# Pedal_SW.net
KiCad netlist of a schematic drawn in Altium Designer
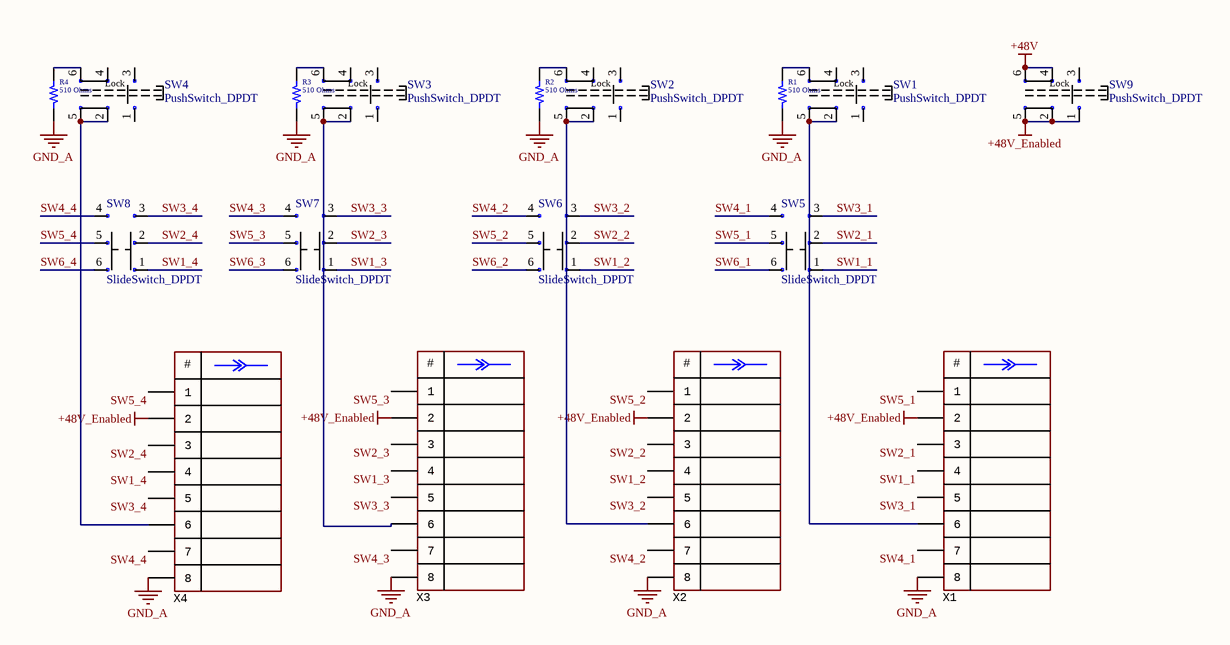
[diagram p0: Pedal_SW.SchDoc]

(export (version "E")
  (design (tool "Eeschema 10.0.6"))
  (components
    (comp (ref "R1")
      (value "510 Ohms")
      (footprint "YAGEO RES 0603_1608")
      (description "RES SMD 510 OHM 1% 1/10W 0603")
      (fields (field (name "PART NUMBER") "AC0603FR-07510RL") (field (name "MANUFACTURER") "Yageo"))
      (libsource (lib "Celestial Altium Library - altium_library") (part "Resistor"))
    )
    (comp (ref "R2")
      (value "510 Ohms")
      (footprint "YAGEO RES 0603_1608")
      (description "RES SMD 510 OHM 1% 1/10W 0603")
      (fields (field (name "PART NUMBER") "AC0603FR-07510RL") (field (name "MANUFACTURER") "Yageo"))
      (libsource (lib "Celestial Altium Library - altium_library") (part "Resistor"))
    )
    (comp (ref "R3")
      (value "510 Ohms")
      (footprint "YAGEO RES 0603_1608")
      (description "RES SMD 510 OHM 1% 1/10W 0603")
      (fields (field (name "PART NUMBER") "AC0603FR-07510RL") (field (name "MANUFACTURER") "Yageo"))
      (libsource (lib "Celestial Altium Library - altium_library") (part "Resistor"))
    )
    (comp (ref "R4")
      (value "510 Ohms")
      (footprint "YAGEO RES 0603_1608")
      (description "RES SMD 510 OHM 1% 1/10W 0603")
      (fields (field (name "PART NUMBER") "AC0603FR-07510RL") (field (name "MANUFACTURER") "Yageo"))
      (libsource (lib "Celestial Altium Library - altium_library") (part "Resistor"))
    )
    (comp (ref "SW1")
      (value "PushSwitch_DPDT")
      (footprint "ProtoStack_H750VBT:TK-6580A-1")
      (libsource (lib "ProtoStack_H750VBT") (part "PushSwitch_DPDT"))
    )
    (comp (ref "SW2")
      (value "PushSwitch_DPDT")
      (footprint "ProtoStack_H750VBT:TK-6580A-1")
      (libsource (lib "ProtoStack_H750VBT") (part "PushSwitch_DPDT"))
    )
    (comp (ref "SW3")
      (value "PushSwitch_DPDT")
      (footprint "ProtoStack_H750VBT:TK-6580A-1")
      (libsource (lib "ProtoStack_H750VBT") (part "PushSwitch_DPDT"))
    )
    (comp (ref "SW4")
      (value "PushSwitch_DPDT")
      (footprint "ProtoStack_H750VBT:TK-6580A-1")
      (libsource (lib "ProtoStack_H750VBT") (part "PushSwitch_DPDT"))
    )
    (comp (ref "SW5")
      (value "SlideSwitch_DPDT")
      (footprint "ProtoStack_H750VBT:SK-22F03-G060")
      (libsource (lib "ProtoStack_H750VBT") (part "SlideSwitch_DPDT"))
    )
    (comp (ref "SW6")
      (value "SlideSwitch_DPDT")
      (footprint "ProtoStack_H750VBT:SK-22F03-G060")
      (libsource (lib "ProtoStack_H750VBT") (part "SlideSwitch_DPDT"))
    )
    (comp (ref "SW7")
      (value "SlideSwitch_DPDT")
      (footprint "ProtoStack_H750VBT:SK-22F03-G060")
      (libsource (lib "ProtoStack_H750VBT") (part "SlideSwitch_DPDT"))
    )
    (comp (ref "SW8")
      (value "SlideSwitch_DPDT")
      (footprint "ProtoStack_H750VBT:SK-22F03-G060")
      (libsource (lib "ProtoStack_H750VBT") (part "SlideSwitch_DPDT"))
    )
    (comp (ref "SW9")
      (value "PushSwitch_DPDT")
      (footprint "ProtoStack_H750VBT:TK-6580A-1")
      (libsource (lib "ProtoStack_H750VBT") (part "PushSwitch_DPDT"))
    )
    (comp (ref "X1")
      (value "~")
      (footprint "CON: PBD-8")
      (fields
        (field (name "MANUFACTURER") "Connfly")
        (field (name "VALUEMANUFACTURERPARTNUMBER") "Connector, 8pin, 2.54mm, 500VAC, 3A")
        (field (name "PARTNUMBER") "PBD-8")
      )
      (libsource (lib "connector") (part "PBD-8"))
    )
    (comp (ref "X2")
      (value "~")
      (footprint "CON: PBD-8")
      (fields
        (field (name "MANUFACTURER") "Connfly")
        (field (name "VALUEMANUFACTURERPARTNUMBER") "Connector, 8pin, 2.54mm, 500VAC, 3A")
        (field (name "PARTNUMBER") "PBD-8")
      )
      (libsource (lib "connector") (part "PBD-8"))
    )
    (comp (ref "X3")
      (value "~")
      (footprint "CON: PBD-8")
      (fields
        (field (name "MANUFACTURER") "Connfly")
        (field (name "VALUEMANUFACTURERPARTNUMBER") "Connector, 8pin, 2.54mm, 500VAC, 3A")
        (field (name "PARTNUMBER") "PBD-8")
      )
      (libsource (lib "connector") (part "PBD-8"))
    )
    (comp (ref "X4")
      (value "~")
      (footprint "CON: PBD-8")
      (fields
        (field (name "MANUFACTURER") "Connfly")
        (field (name "VALUEMANUFACTURERPARTNUMBER") "Connector, 8pin, 2.54mm, 500VAC, 3A")
        (field (name "PARTNUMBER") "PBD-8")
      )
      (libsource (lib "connector") (part "PBD-8"))
    )
  )
  (nets
    (net (code "1") (name "+48V") (class "Default")
      (node (ref "SW9") (pin "4") (pinfunction "4_4") (pintype "passive"))
      (node (ref "SW9") (pin "6") (pinfunction "6_6") (pintype "passive"))
    )
    (net (code "2") (name "+48V_Enabled") (class "Default")
      (node (ref "SW9") (pin "1") (pinfunction "1_1") (pintype "passive"))
      (node (ref "SW9") (pin "2") (pinfunction "2_2") (pintype "passive"))
      (node (ref "SW9") (pin "5") (pinfunction "5_5") (pintype "passive"))
      (node (ref "X1") (pin "2") (pinfunction "2_2") (pintype "passive"))
      (node (ref "X2") (pin "2") (pinfunction "2_2") (pintype "passive"))
      (node (ref "X3") (pin "2") (pinfunction "2_2") (pintype "passive"))
      (node (ref "X4") (pin "2") (pinfunction "2_2") (pintype "passive"))
    )
    (net (code "3") (name "/SW1_1") (class "Default")
      (node (ref "SW5") (pin "1") (pinfunction "1_1") (pintype "passive"))
      (node (ref "X1") (pin "4") (pinfunction "4_4") (pintype "power_in"))
    )
    (net (code "4") (name "/SW1_2") (class "Default")
      (node (ref "SW6") (pin "1") (pinfunction "1_1") (pintype "passive"))
      (node (ref "X2") (pin "4") (pinfunction "4_4") (pintype "power_in"))
    )
    (net (code "5") (name "/SW1_3") (class "Default")
      (node (ref "SW7") (pin "1") (pinfunction "1_1") (pintype "passive"))
      (node (ref "X3") (pin "4") (pinfunction "4_4") (pintype "power_in"))
    )
    (net (code "6") (name "/SW1_4") (class "Default")
      (node (ref "SW8") (pin "1") (pinfunction "1_1") (pintype "passive"))
      (node (ref "X4") (pin "4") (pinfunction "4_4") (pintype "power_in"))
    )
    (net (code "7") (name "/SW2_1") (class "Default")
      (node (ref "SW5") (pin "2") (pinfunction "2_2") (pintype "passive"))
      (node (ref "X1") (pin "3") (pinfunction "3_3") (pintype "power_in"))
    )
    (net (code "8") (name "/SW2_2") (class "Default")
      (node (ref "SW6") (pin "2") (pinfunction "2_2") (pintype "passive"))
      (node (ref "X2") (pin "3") (pinfunction "3_3") (pintype "power_in"))
    )
    (net (code "9") (name "/SW2_3") (class "Default")
      (node (ref "SW7") (pin "2") (pinfunction "2_2") (pintype "passive"))
      (node (ref "X3") (pin "3") (pinfunction "3_3") (pintype "power_in"))
    )
    (net (code "10") (name "/SW2_4") (class "Default")
      (node (ref "SW8") (pin "2") (pinfunction "2_2") (pintype "passive"))
      (node (ref "X4") (pin "3") (pinfunction "3_3") (pintype "power_in"))
    )
    (net (code "11") (name "/SW3_1") (class "Default")
      (node (ref "SW5") (pin "3") (pinfunction "3_3") (pintype "passive"))
      (node (ref "X1") (pin "5") (pinfunction "5_5") (pintype "power_in"))
    )
    (net (code "12") (name "/SW3_2") (class "Default")
      (node (ref "SW6") (pin "3") (pinfunction "3_3") (pintype "passive"))
      (node (ref "X2") (pin "5") (pinfunction "5_5") (pintype "power_in"))
    )
    (net (code "13") (name "/SW3_3") (class "Default")
      (node (ref "SW7") (pin "3") (pinfunction "3_3") (pintype "passive"))
      (node (ref "X3") (pin "5") (pinfunction "5_5") (pintype "power_in"))
    )
    (net (code "14") (name "/SW3_4") (class "Default")
      (node (ref "SW8") (pin "3") (pinfunction "3_3") (pintype "passive"))
      (node (ref "X4") (pin "5") (pinfunction "5_5") (pintype "power_in"))
    )
    (net (code "15") (name "/SW4_1") (class "Default")
      (node (ref "SW5") (pin "4") (pinfunction "4_4") (pintype "passive"))
      (node (ref "X1") (pin "7") (pinfunction "7_7") (pintype "power_in"))
    )
    (net (code "16") (name "/SW4_2") (class "Default")
      (node (ref "SW6") (pin "4") (pinfunction "4_4") (pintype "passive"))
      (node (ref "X2") (pin "7") (pinfunction "7_7") (pintype "power_in"))
    )
    (net (code "17") (name "/SW4_3") (class "Default")
      (node (ref "SW7") (pin "4") (pinfunction "4_4") (pintype "passive"))
      (node (ref "X3") (pin "7") (pinfunction "7_7") (pintype "power_in"))
    )
    (net (code "18") (name "/SW4_4") (class "Default")
      (node (ref "SW8") (pin "4") (pinfunction "4_4") (pintype "passive"))
      (node (ref "X4") (pin "7") (pinfunction "7_7") (pintype "power_in"))
    )
    (net (code "19") (name "/SW5_1") (class "Default")
      (node (ref "SW5") (pin "5") (pinfunction "5_5") (pintype "passive"))
      (node (ref "X1") (pin "1") (pinfunction "1_1") (pintype "passive"))
    )
    (net (code "20") (name "/SW5_2") (class "Default")
      (node (ref "SW6") (pin "5") (pinfunction "5_5") (pintype "passive"))
      (node (ref "X2") (pin "1") (pinfunction "1_1") (pintype "passive"))
    )
    (net (code "21") (name "/SW5_3") (class "Default")
      (node (ref "SW7") (pin "5") (pinfunction "5_5") (pintype "passive"))
      (node (ref "X3") (pin "1") (pinfunction "1_1") (pintype "passive"))
    )
    (net (code "22") (name "/SW5_4") (class "Default")
      (node (ref "SW8") (pin "5") (pinfunction "5_5") (pintype "passive"))
      (node (ref "X4") (pin "1") (pinfunction "1_1") (pintype "passive"))
    )
    (net (code "23") (name "/SW6_1") (class "Default")
      (node (ref "SW5") (pin "6") (pinfunction "6_6") (pintype "passive"))
    )
    (net (code "24") (name "/SW6_2") (class "Default")
      (node (ref "SW6") (pin "6") (pinfunction "6_6") (pintype "passive"))
    )
    (net (code "25") (name "/SW6_3") (class "Default")
      (node (ref "SW7") (pin "6") (pinfunction "6_6") (pintype "passive"))
    )
    (net (code "26") (name "/SW6_4") (class "Default")
      (node (ref "SW8") (pin "6") (pinfunction "6_6") (pintype "passive"))
    )
    (net (code "27") (name "GND_A") (class "Default")
      (node (ref "R1") (pin "2") (pinfunction "2_2") (pintype "passive"))
      (node (ref "R2") (pin "2") (pinfunction "2_2") (pintype "passive"))
      (node (ref "R3") (pin "2") (pinfunction "2_2") (pintype "passive"))
      (node (ref "R4") (pin "2") (pinfunction "2_2") (pintype "passive"))
      (node (ref "X1") (pin "8") (pinfunction "8_8") (pintype "power_in"))
      (node (ref "X2") (pin "8") (pinfunction "8_8") (pintype "power_in"))
      (node (ref "X3") (pin "8") (pinfunction "8_8") (pintype "power_in"))
      (node (ref "X4") (pin "8") (pinfunction "8_8") (pintype "power_in"))
    )
    (net (code "28") (name "Net-(R1-Pad1)") (class "Default")
      (node (ref "R1") (pin "1") (pinfunction "1_1") (pintype "passive"))
      (node (ref "SW1") (pin "6") (pinfunction "6_6") (pintype "passive"))
    )
    (net (code "29") (name "Net-(R2-Pad1)") (class "Default")
      (node (ref "R2") (pin "1") (pinfunction "1_1") (pintype "passive"))
      (node (ref "SW2") (pin "6") (pinfunction "6_6") (pintype "passive"))
    )
    (net (code "30") (name "Net-(R3-Pad1)") (class "Default")
      (node (ref "R3") (pin "1") (pinfunction "1_1") (pintype "passive"))
      (node (ref "SW3") (pin "6") (pinfunction "6_6") (pintype "passive"))
    )
    (net (code "31") (name "Net-(R4-Pad1)") (class "Default")
      (node (ref "R4") (pin "1") (pinfunction "1_1") (pintype "passive"))
      (node (ref "SW4") (pin "6") (pinfunction "6_6") (pintype "passive"))
    )
    (net (code "32") (name "Net-(SW1-Pad2)") (class "Default")
      (node (ref "SW1") (pin "2") (pinfunction "2_2") (pintype "passive"))
      (node (ref "SW1") (pin "5") (pinfunction "5_5") (pintype "passive"))
      (node (ref "X1") (pin "6") (pinfunction "6_6") (pintype "power_in"))
    )
    (net (code "33") (name "Net-(SW2-Pad2)") (class "Default")
      (node (ref "SW2") (pin "2") (pinfunction "2_2") (pintype "passive"))
      (node (ref "SW2") (pin "5") (pinfunction "5_5") (pintype "passive"))
      (node (ref "X2") (pin "6") (pinfunction "6_6") (pintype "power_in"))
    )
    (net (code "34") (name "Net-(SW3-Pad2)") (class "Default")
      (node (ref "SW3") (pin "2") (pinfunction "2_2") (pintype "passive"))
      (node (ref "SW3") (pin "5") (pinfunction "5_5") (pintype "passive"))
      (node (ref "X3") (pin "6") (pinfunction "6_6") (pintype "power_in"))
    )
    (net (code "35") (name "Net-(SW4-Pad2)") (class "Default")
      (node (ref "SW4") (pin "2") (pinfunction "2_2") (pintype "passive"))
      (node (ref "SW4") (pin "5") (pinfunction "5_5") (pintype "passive"))
      (node (ref "X4") (pin "6") (pinfunction "6_6") (pintype "power_in"))
    )
    (net (code "36") (name "unconnected-(SW1-Pad1)") (class "Default")
      (node (ref "SW1") (pin "1") (pinfunction "1_1") (pintype "passive"))
    )
    (net (code "37") (name "unconnected-(SW1-Pad3)") (class "Default")
      (node (ref "SW1") (pin "3") (pinfunction "3_3") (pintype "passive"))
    )
    (net (code "38") (name "unconnected-(SW1-Pad4)") (class "Default")
      (node (ref "SW1") (pin "4") (pinfunction "4_4") (pintype "passive"))
    )
    (net (code "39") (name "unconnected-(SW2-Pad1)") (class "Default")
      (node (ref "SW2") (pin "1") (pinfunction "1_1") (pintype "passive"))
    )
    (net (code "40") (name "unconnected-(SW2-Pad3)") (class "Default")
      (node (ref "SW2") (pin "3") (pinfunction "3_3") (pintype "passive"))
    )
    (net (code "41") (name "unconnected-(SW2-Pad4)") (class "Default")
      (node (ref "SW2") (pin "4") (pinfunction "4_4") (pintype "passive"))
    )
    (net (code "42") (name "unconnected-(SW3-Pad1)") (class "Default")
      (node (ref "SW3") (pin "1") (pinfunction "1_1") (pintype "passive"))
    )
    (net (code "43") (name "unconnected-(SW3-Pad3)") (class "Default")
      (node (ref "SW3") (pin "3") (pinfunction "3_3") (pintype "passive"))
    )
    (net (code "44") (name "unconnected-(SW3-Pad4)") (class "Default")
      (node (ref "SW3") (pin "4") (pinfunction "4_4") (pintype "passive"))
    )
    (net (code "45") (name "unconnected-(SW4-Pad1)") (class "Default")
      (node (ref "SW4") (pin "1") (pinfunction "1_1") (pintype "passive"))
    )
    (net (code "46") (name "unconnected-(SW4-Pad3)") (class "Default")
      (node (ref "SW4") (pin "3") (pinfunction "3_3") (pintype "passive"))
    )
    (net (code "47") (name "unconnected-(SW4-Pad4)") (class "Default")
      (node (ref "SW4") (pin "4") (pinfunction "4_4") (pintype "passive"))
    )
    (net (code "48") (name "unconnected-(SW9-Pad3)") (class "Default")
      (node (ref "SW9") (pin "3") (pinfunction "3_3") (pintype "passive"))
    )
  )
)
